# esp8266-board.net
KiCad netlist of a schematic drawn in EAGLE
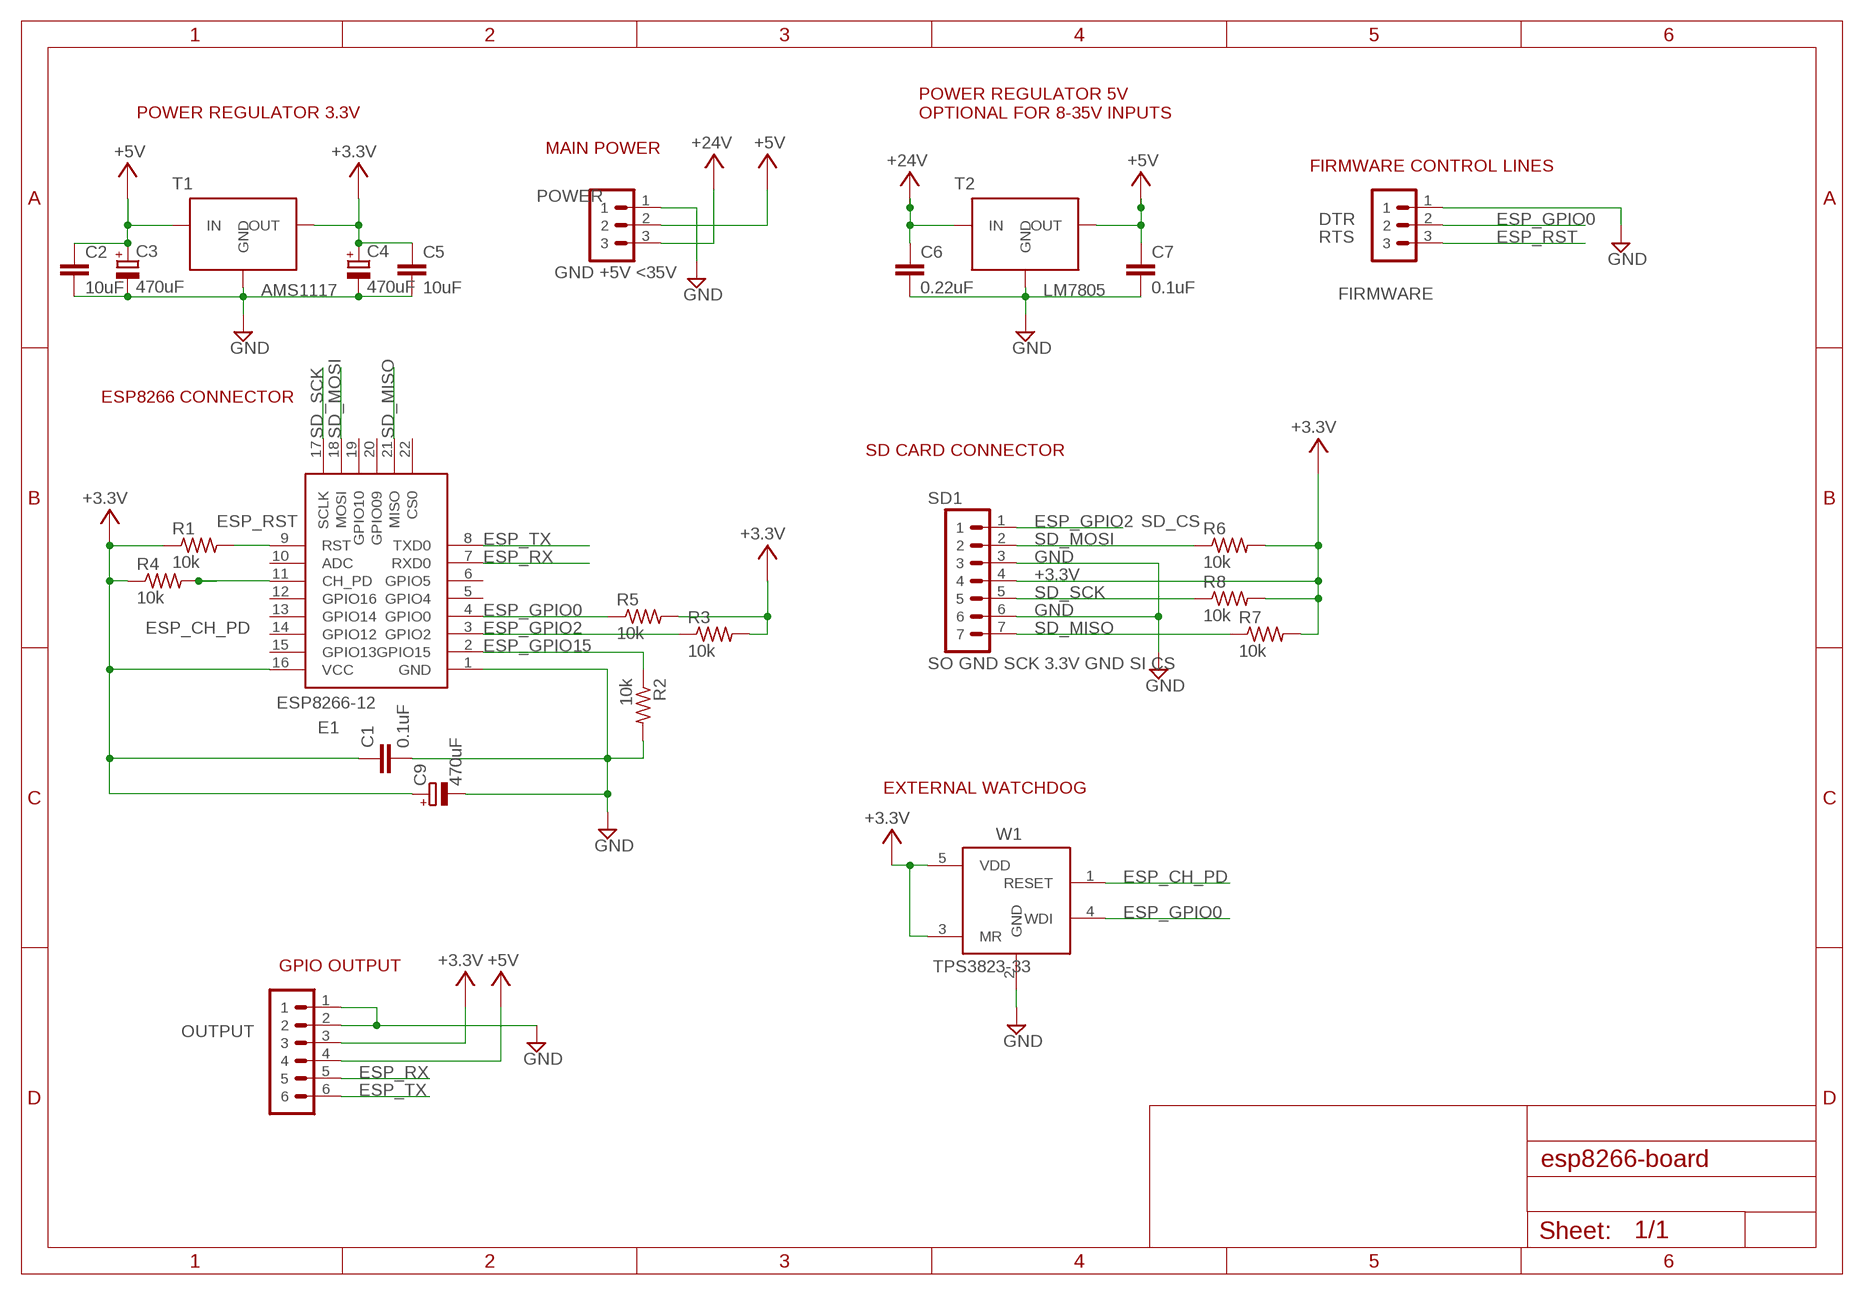
[diagram p0: schematic, sheet 1]

(export (version "E")
  (design (tool "Eeschema 10.0.6"))
  (components
    (comp (ref "C1")
      (value "0.1uF")
      (footprint "eagle-import:C2.5-2")
      (libsource (lib "eagle-import") (part "C2.5/2"))
    )
    (comp (ref "C2")
      (value "10uF")
      (footprint "eagle-import:C2.5-2")
      (libsource (lib "eagle-import") (part "C2.5/2"))
    )
    (comp (ref "C3")
      (value "470uF")
      (footprint "eagle-import:E2,5-6E")
      (libsource (lib "eagle-import") (part "CPOL-EUE2,5-6E"))
    )
    (comp (ref "C4")
      (value "470uF")
      (footprint "eagle-import:E2,5-6E")
      (fields (field (name "MPN") "FK18X5R0J106M"))
      (libsource (lib "eagle-import") (part "CPOL-EUE2,5-6E"))
    )
    (comp (ref "C5")
      (value "10uF")
      (footprint "eagle-import:C2.5-2")
      (libsource (lib "eagle-import") (part "C2.5/2"))
    )
    (comp (ref "C6")
      (value "0.22uF")
      (footprint "eagle-import:C2.5-2")
      (fields (field (name "MPN") "1C10Z5U104M050B"))
      (libsource (lib "eagle-import") (part "C2.5/2"))
    )
    (comp (ref "C7")
      (value "0.1uF")
      (footprint "eagle-import:C2.5-2")
      (fields (field (name "MPN") "FK18X5R0J106M"))
      (libsource (lib "eagle-import") (part "C2.5/2"))
    )
    (comp (ref "C9")
      (value "470uF")
      (footprint "eagle-import:E2,5-6")
      (libsource (lib "eagle-import") (part "CPOL-EUE2.5-6"))
    )
    (comp (ref "E1")
      (value "ESP8266-12")
      (footprint "eagle-import:ESP8266-12")
      (libsource (lib "eagle-import") (part "ESP8266-12"))
    )
    (comp (ref "FIRMWARE")
      (value "GND DTR RTS")
      (footprint "eagle-import:PIN-HEADER-3PIN")
      (libsource (lib "eagle-import") (part "PIN-HEADER-3PIN"))
    )
    (comp (ref "OUTPUT")
      (value "GND GND 3.3V 5V RX TX")
      (footprint "eagle-import:PIN-HEADER-6PIN")
      (libsource (lib "eagle-import") (part "PIN-HEADER-6PIN"))
    )
    (comp (ref "POWER")
      (value "GND +5V <35V")
      (footprint "eagle-import:PIN-HEADER-3PIN")
      (libsource (lib "eagle-import") (part "PIN-HEADER-3PIN"))
    )
    (comp (ref "R1")
      (value "10k")
      (footprint "eagle-import:RESISTOR-V1")
      (libsource (lib "eagle-import") (part "RESISTORV1"))
    )
    (comp (ref "R2")
      (value "10k")
      (footprint "eagle-import:RESISTOR-V1")
      (libsource (lib "eagle-import") (part "RESISTORV1"))
    )
    (comp (ref "R3")
      (value "10k")
      (footprint "eagle-import:RESISTOR-V1")
      (libsource (lib "eagle-import") (part "RESISTORV1"))
    )
    (comp (ref "R4")
      (value "10k")
      (footprint "eagle-import:RESISTOR-V1")
      (libsource (lib "eagle-import") (part "RESISTORV1"))
    )
    (comp (ref "R5")
      (value "10k")
      (footprint "eagle-import:RESISTOR-V1")
      (libsource (lib "eagle-import") (part "RESISTORV1"))
    )
    (comp (ref "R6")
      (value "10k")
      (footprint "eagle-import:RESISTOR-V1")
      (libsource (lib "eagle-import") (part "RESISTORV1"))
    )
    (comp (ref "R7")
      (value "10k")
      (footprint "eagle-import:RESISTOR-V1")
      (libsource (lib "eagle-import") (part "RESISTORV1"))
    )
    (comp (ref "R8")
      (value "10k")
      (footprint "eagle-import:RESISTOR-V1")
      (libsource (lib "eagle-import") (part "RESISTORV1"))
    )
    (comp (ref "SD1")
      (value "SO GND SCK 3.3V GND SI CS")
      (footprint "eagle-import:PIN-HEADER-7PIN")
      (libsource (lib "eagle-import") (part "PIN-HEADER-7PIN"))
    )
    (comp (ref "T1")
      (value "AMS1117")
      (footprint "eagle-import:SOT-223")
      (fields (field (name "MPN") "LM2937ET-3.3"))
      (libsource (lib "eagle-import") (part "AMS1117"))
    )
    (comp (ref "T2")
      (value "LM7805")
      (footprint "eagle-import:TO-220")
      (fields (field (name "MPN") "LM2937ET-3.3"))
      (libsource (lib "eagle-import") (part "LM7805"))
    )
    (comp (ref "W1")
      (value "TPS3823-33")
      (footprint "eagle-import:SOT23-5_TSOT25")
      (libsource (lib "eagle-import") (part "TPS382X"))
    )
  )
  (nets
    (net (code "1") (name "+3.3V") (class "Default")
      (node (ref "C1") (pin "1") (pinfunction "1_1") (pintype "passive"))
      (node (ref "C4") (pin "+") (pinfunction "+_+") (pintype "passive"))
      (node (ref "C5") (pin "1") (pinfunction "1_1") (pintype "passive"))
      (node (ref "C9") (pin "+") (pinfunction "+_+") (pintype "passive"))
      (node (ref "E1") (pin "16") (pinfunction "VCC_16") (pintype "input"))
      (node (ref "OUTPUT") (pin "3") (pinfunction "3_3") (pintype "passive"))
      (node (ref "R1") (pin "1") (pinfunction "1_1") (pintype "passive"))
      (node (ref "R3") (pin "2") (pinfunction "2_2") (pintype "passive"))
      (node (ref "R4") (pin "1") (pinfunction "1_1") (pintype "passive"))
      (node (ref "R5") (pin "2") (pinfunction "2_2") (pintype "passive"))
      (node (ref "R6") (pin "2") (pinfunction "2_2") (pintype "passive"))
      (node (ref "R7") (pin "2") (pinfunction "2_2") (pintype "passive"))
      (node (ref "R8") (pin "2") (pinfunction "2_2") (pintype "passive"))
      (node (ref "SD1") (pin "4") (pinfunction "4_4") (pintype "passive"))
      (node (ref "T1") (pin "2") (pinfunction "OUT_2") (pintype "power_in"))
      (node (ref "W1") (pin "3") (pinfunction "MR_3") (pintype "input"))
      (node (ref "W1") (pin "5") (pinfunction "VDD_5") (pintype "power_in"))
    )
    (net (code "2") (name "+5V") (class "Default")
      (node (ref "C2") (pin "1") (pinfunction "1_1") (pintype "passive"))
      (node (ref "C3") (pin "+") (pinfunction "+_+") (pintype "passive"))
      (node (ref "C7") (pin "1") (pinfunction "1_1") (pintype "passive"))
      (node (ref "OUTPUT") (pin "4") (pinfunction "4_4") (pintype "passive"))
      (node (ref "POWER") (pin "2") (pinfunction "2_2") (pintype "passive"))
      (node (ref "T1") (pin "3") (pinfunction "IN_3") (pintype "power_in"))
      (node (ref "T2") (pin "OUTPUT") (pinfunction "OUT_OUTPUT") (pintype "power_in"))
    )
    (net (code "3") (name "+24V") (class "Default")
      (node (ref "C6") (pin "1") (pinfunction "1_1") (pintype "passive"))
      (node (ref "POWER") (pin "3") (pinfunction "3_3") (pintype "passive"))
      (node (ref "T2") (pin "INPUT") (pinfunction "IN_INPUT") (pintype "power_in"))
    )
    (net (code "4") (name "/ESP_CH_PD") (class "Default")
      (node (ref "E1") (pin "11") (pinfunction "CH_PD_11") (pintype "input"))
      (node (ref "R4") (pin "2") (pinfunction "2_2") (pintype "passive"))
      (node (ref "W1") (pin "1") (pinfunction "RESET_1") (pintype "output"))
    )
    (net (code "5") (name "/ESP_GPIO0") (class "Default")
      (node (ref "E1") (pin "4") (pinfunction "GPIO0_4") (pintype "input"))
      (node (ref "FIRMWARE") (pin "2") (pinfunction "2_2") (pintype "passive"))
      (node (ref "R5") (pin "1") (pinfunction "1_1") (pintype "passive"))
      (node (ref "W1") (pin "4") (pinfunction "WDI_4") (pintype "input"))
    )
    (net (code "6") (name "/ESP_GPIO2") (class "Default")
      (node (ref "E1") (pin "3") (pinfunction "GPIO2_3") (pintype "input"))
      (node (ref "R3") (pin "1") (pinfunction "1_1") (pintype "passive"))
      (node (ref "SD1") (pin "1") (pinfunction "1_1") (pintype "passive"))
    )
    (net (code "7") (name "/ESP_GPIO15") (class "Default")
      (node (ref "E1") (pin "2") (pinfunction "GPIO15_2") (pintype "input"))
      (node (ref "R2") (pin "1") (pinfunction "1_1") (pintype "passive"))
    )
    (net (code "8") (name "/ESP_RST") (class "Default")
      (node (ref "E1") (pin "9") (pinfunction "RST_9") (pintype "input"))
      (node (ref "FIRMWARE") (pin "3") (pinfunction "3_3") (pintype "passive"))
      (node (ref "R1") (pin "2") (pinfunction "2_2") (pintype "passive"))
    )
    (net (code "9") (name "/ESP_RX") (class "Default")
      (node (ref "E1") (pin "7") (pinfunction "RXD0_7") (pintype "power_in"))
      (node (ref "OUTPUT") (pin "5") (pinfunction "5_5") (pintype "passive"))
    )
    (net (code "10") (name "/ESP_TX") (class "Default")
      (node (ref "E1") (pin "8") (pinfunction "TXD0_8") (pintype "bidirectional"))
      (node (ref "OUTPUT") (pin "6") (pinfunction "6_6") (pintype "passive"))
    )
    (net (code "11") (name "/GPIO5") (class "Default")
      (node (ref "E1") (pin "6") (pinfunction "GPIO5_6") (pintype "power_in"))
    )
    (net (code "12") (name "/SD_MISO") (class "Default")
      (node (ref "E1") (pin "21") (pinfunction "MISO_21") (pintype "bidirectional"))
      (node (ref "R7") (pin "1") (pinfunction "1_1") (pintype "passive"))
      (node (ref "SD1") (pin "7") (pinfunction "7_7") (pintype "passive"))
    )
    (net (code "13") (name "/SD_MOSI") (class "Default")
      (node (ref "E1") (pin "18") (pinfunction "MOSI_18") (pintype "bidirectional"))
      (node (ref "R6") (pin "1") (pinfunction "1_1") (pintype "passive"))
      (node (ref "SD1") (pin "2") (pinfunction "2_2") (pintype "passive"))
    )
    (net (code "14") (name "/SD_SCK") (class "Default")
      (node (ref "E1") (pin "17") (pinfunction "SCLK_17") (pintype "bidirectional"))
      (node (ref "R8") (pin "1") (pinfunction "1_1") (pintype "passive"))
      (node (ref "SD1") (pin "5") (pinfunction "5_5") (pintype "passive"))
    )
    (net (code "15") (name "GND") (class "Default")
      (node (ref "C1") (pin "2") (pinfunction "2_2") (pintype "passive"))
      (node (ref "C2") (pin "2") (pinfunction "2_2") (pintype "passive"))
      (node (ref "C3") (pin "-") (pinfunction "-_-") (pintype "passive"))
      (node (ref "C4") (pin "-") (pinfunction "-_-") (pintype "passive"))
      (node (ref "C5") (pin "2") (pinfunction "2_2") (pintype "passive"))
      (node (ref "C6") (pin "2") (pinfunction "2_2") (pintype "passive"))
      (node (ref "C7") (pin "2") (pinfunction "2_2") (pintype "passive"))
      (node (ref "C9") (pin "-") (pinfunction "-_-") (pintype "passive"))
      (node (ref "E1") (pin "1") (pinfunction "GND_1") (pintype "input"))
      (node (ref "FIRMWARE") (pin "1") (pinfunction "1_1") (pintype "passive"))
      (node (ref "OUTPUT") (pin "1") (pinfunction "1_1") (pintype "passive"))
      (node (ref "OUTPUT") (pin "2") (pinfunction "2_2") (pintype "passive"))
      (node (ref "POWER") (pin "1") (pinfunction "1_1") (pintype "passive"))
      (node (ref "R2") (pin "2") (pinfunction "2_2") (pintype "passive"))
      (node (ref "SD1") (pin "3") (pinfunction "3_3") (pintype "passive"))
      (node (ref "SD1") (pin "6") (pinfunction "6_6") (pintype "passive"))
      (node (ref "T1") (pin "1") (pinfunction "GND_1") (pintype "power_in"))
      (node (ref "T2") (pin "GND") (pinfunction "GND_GND") (pintype "power_in"))
      (node (ref "W1") (pin "2") (pinfunction "GND_2") (pintype "power_in"))
    )
    (net (code "16") (name "unconnected-(E1-ADC-Pad10)") (class "Default")
      (node (ref "E1") (pin "10") (pinfunction "ADC_10") (pintype "input"))
    )
    (net (code "17") (name "unconnected-(E1-CS0-Pad22)") (class "Default")
      (node (ref "E1") (pin "22") (pinfunction "CS0_22") (pintype "bidirectional"))
    )
    (net (code "18") (name "unconnected-(E1-GPIO4-Pad5)") (class "Default")
      (node (ref "E1") (pin "5") (pinfunction "GPIO4_5") (pintype "input"))
    )
    (net (code "19") (name "unconnected-(E1-GPIO09-Pad20)") (class "Default")
      (node (ref "E1") (pin "20") (pinfunction "GPIO09_20") (pintype "bidirectional"))
    )
    (net (code "20") (name "unconnected-(E1-GPIO10-Pad19)") (class "Default")
      (node (ref "E1") (pin "19") (pinfunction "GPIO10_19") (pintype "bidirectional"))
    )
    (net (code "21") (name "unconnected-(E1-GPIO12-Pad14)") (class "Default")
      (node (ref "E1") (pin "14") (pinfunction "GPIO12_14") (pintype "input"))
    )
    (net (code "22") (name "unconnected-(E1-GPIO13-Pad15)") (class "Default")
      (node (ref "E1") (pin "15") (pinfunction "GPIO13_15") (pintype "input"))
    )
    (net (code "23") (name "unconnected-(E1-GPIO14-Pad13)") (class "Default")
      (node (ref "E1") (pin "13") (pinfunction "GPIO14_13") (pintype "input"))
    )
    (net (code "24") (name "unconnected-(E1-GPIO16-Pad12)") (class "Default")
      (node (ref "E1") (pin "12") (pinfunction "GPIO16_12") (pintype "input"))
    )
  )
)
